# interface2.net
KiCad netlist of a schematic drawn in Altium Designer
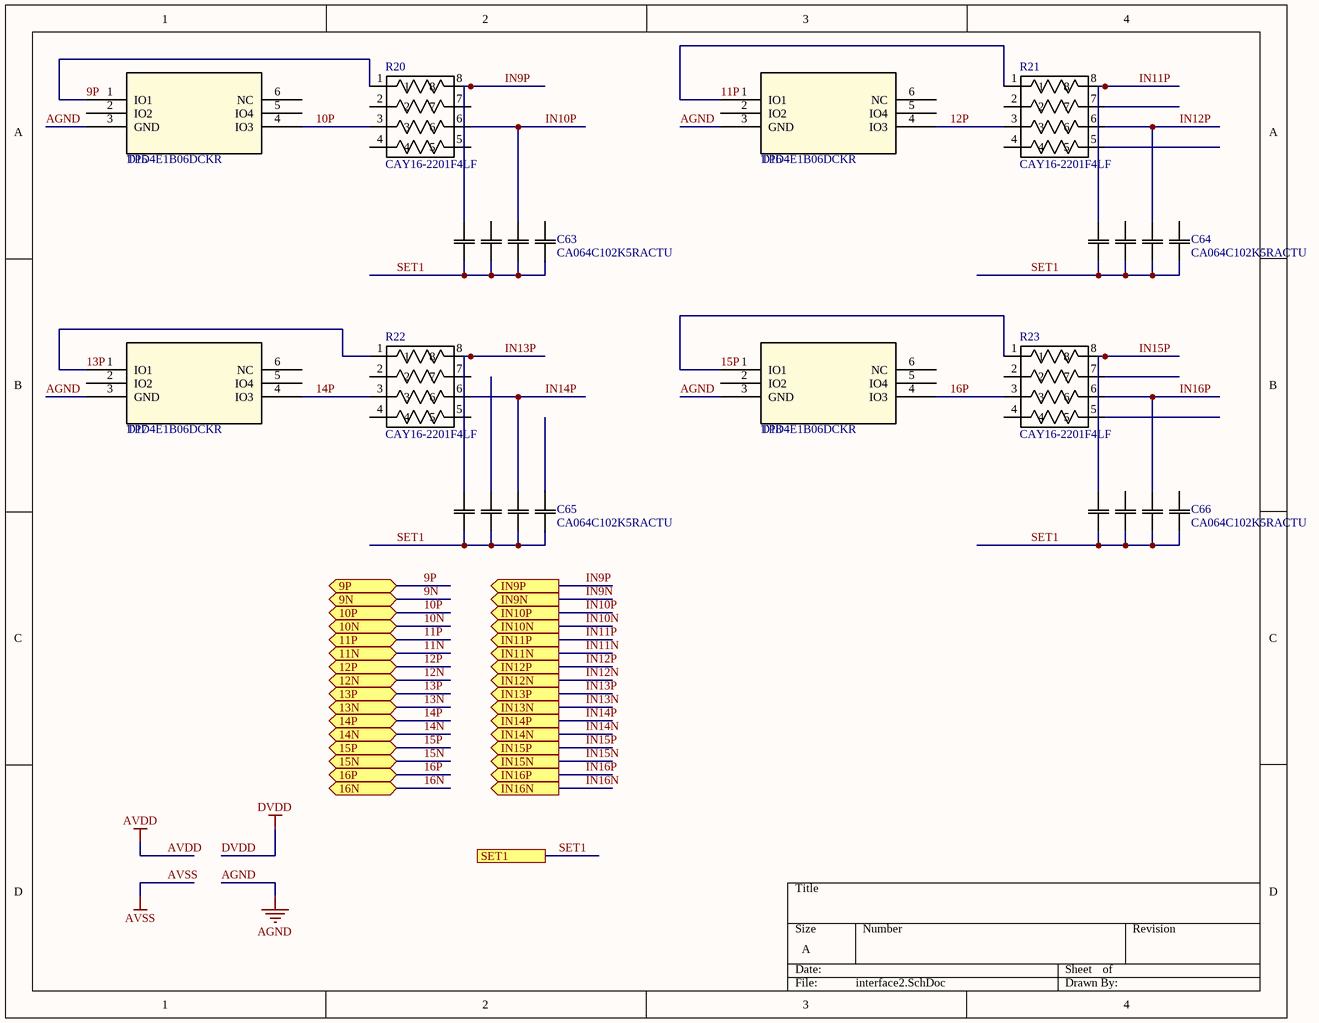
[diagram p0: interface2.SchDoc]

(export (version "E")
  (design (tool "Eeschema 10.0.6"))
  (components
    (comp (ref "C63")
      (value "CA064C102K5RACTU")
      (footprint "CA064")
      (description "CAP ARRAY 1000PF 50V X7R 0612")
      (fields (field (name "TOLERANCE") "10%"))
      (libsource (lib "EE_smallOB_BW_v1.0") (part "CA064C102K5RACTU"))
    )
    (comp (ref "C64")
      (value "CA064C102K5RACTU")
      (footprint "CA064")
      (description "CAP ARRAY 1000PF 50V X7R 0612")
      (fields (field (name "TOLERANCE") "10%"))
      (libsource (lib "EE_smallOB_BW_v1.0") (part "CA064C102K5RACTU"))
    )
    (comp (ref "C65")
      (value "CA064C102K5RACTU")
      (footprint "CA064")
      (description "CAP ARRAY 1000PF 50V X7R 0612")
      (fields (field (name "TOLERANCE") "10%"))
      (libsource (lib "EE_smallOB_BW_v1.0") (part "CA064C102K5RACTU"))
    )
    (comp (ref "C66")
      (value "CA064C102K5RACTU")
      (footprint "CA064")
      (description "CAP ARRAY 1000PF 50V X7R 0612")
      (fields (field (name "TOLERANCE") "10%"))
      (libsource (lib "EE_smallOB_BW_v1.0") (part "CA064C102K5RACTU"))
    )
    (comp (ref "D15")
      (value "TPD4E1B06DCKR")
      (footprint "DCK6")
      (description "TVS DIODE 5.5VWM 14.5VC SC70-6")
      (libsource (lib "EE_smallOB_BW_v1.0") (part "TPD4E1B06DCKR"))
    )
    (comp (ref "D16")
      (value "TPD4E1B06DCKR")
      (footprint "DCK6")
      (description "TVS DIODE 5.5VWM 14.5VC SC70-6")
      (libsource (lib "EE_smallOB_BW_v1.0") (part "TPD4E1B06DCKR"))
    )
    (comp (ref "D17")
      (value "TPD4E1B06DCKR")
      (footprint "DCK6")
      (description "TVS DIODE 5.5VWM 14.5VC SC70-6")
      (libsource (lib "EE_smallOB_BW_v1.0") (part "TPD4E1B06DCKR"))
    )
    (comp (ref "D18")
      (value "TPD4E1B06DCKR")
      (footprint "DCK6")
      (description "TVS DIODE 5.5VWM 14.5VC SC70-6")
      (libsource (lib "EE_smallOB_BW_v1.0") (part "TPD4E1B06DCKR"))
    )
    (comp (ref "R20")
      (value "CAY16-2201F4LF")
      (footprint "*RESCAXE80P320X160-8N")
      (description "BOURNS         CAY16-2201F4LF             RESISTOR, ARRAY-4, 2.2KOHM, 5%, SMD")
      (fields (field (name "TOLERANCE") "1%"))
      (libsource (lib "EE_smallOB_BW_v1.0") (part "CAY16-2201F4LF"))
    )
    (comp (ref "R21")
      (value "CAY16-2201F4LF")
      (footprint "*RESCAXE80P320X160-8N")
      (description "BOURNS         CAY16-2201F4LF             RESISTOR, ARRAY-4, 2.2KOHM, 5%, SMD")
      (fields (field (name "TOLERANCE") "1%"))
      (libsource (lib "EE_smallOB_BW_v1.0") (part "CAY16-2201F4LF"))
    )
    (comp (ref "R22")
      (value "CAY16-2201F4LF")
      (footprint "*RESCAXE80P320X160-8N")
      (description "BOURNS         CAY16-2201F4LF             RESISTOR, ARRAY-4, 2.2KOHM, 5%, SMD")
      (fields (field (name "TOLERANCE") "1%"))
      (libsource (lib "EE_smallOB_BW_v1.0") (part "CAY16-2201F4LF"))
    )
    (comp (ref "R23")
      (value "CAY16-2201F4LF")
      (footprint "*RESCAXE80P320X160-8N")
      (description "BOURNS         CAY16-2201F4LF             RESISTOR, ARRAY-4, 2.2KOHM, 5%, SMD")
      (fields (field (name "TOLERANCE") "1%"))
      (libsource (lib "EE_smallOB_BW_v1.0") (part "CAY16-2201F4LF"))
    )
  )
  (nets
    (net (code "2") (name "/9P") (class "Default")
      (node (ref "D15") (pin "1") (pinfunction "IO1_1") (pintype "passive"))
      (node (ref "R20") (pin "1") (pinfunction "1_1") (pintype "passive"))
    )
    (net (code "4") (name "/10P") (class "Default")
      (node (ref "D15") (pin "4") (pinfunction "IO3_4") (pintype "passive"))
      (node (ref "R20") (pin "3") (pinfunction "3_3") (pintype "passive"))
    )
    (net (code "6") (name "/11P") (class "Default")
      (node (ref "D16") (pin "1") (pinfunction "IO1_1") (pintype "passive"))
      (node (ref "R21") (pin "1") (pinfunction "1_1") (pintype "passive"))
    )
    (net (code "8") (name "/12P") (class "Default")
      (node (ref "D16") (pin "4") (pinfunction "IO3_4") (pintype "passive"))
      (node (ref "R21") (pin "3") (pinfunction "3_3") (pintype "passive"))
    )
    (net (code "10") (name "/13P") (class "Default")
      (node (ref "D17") (pin "1") (pinfunction "IO1_1") (pintype "passive"))
      (node (ref "R22") (pin "1") (pinfunction "1_1") (pintype "passive"))
    )
    (net (code "12") (name "/14P") (class "Default")
      (node (ref "D17") (pin "4") (pinfunction "IO3_4") (pintype "passive"))
      (node (ref "R22") (pin "3") (pinfunction "3_3") (pintype "passive"))
    )
    (net (code "14") (name "/15P") (class "Default")
      (node (ref "D18") (pin "1") (pinfunction "IO1_1") (pintype "passive"))
      (node (ref "R23") (pin "1") (pinfunction "1_1") (pintype "passive"))
    )
    (net (code "16") (name "/16P") (class "Default")
      (node (ref "D18") (pin "4") (pinfunction "IO3_4") (pintype "passive"))
      (node (ref "R23") (pin "3") (pinfunction "3_3") (pintype "passive"))
    )
    (net (code "18") (name "/IN9P") (class "Default")
      (node (ref "C63") (pin "8") (pinfunction "8_8") (pintype "passive"))
      (node (ref "R20") (pin "8") (pinfunction "8_8") (pintype "passive"))
    )
    (net (code "20") (name "/IN10P") (class "Default")
      (node (ref "C63") (pin "6") (pinfunction "6_6") (pintype "passive"))
      (node (ref "R20") (pin "6") (pinfunction "6_6") (pintype "passive"))
    )
    (net (code "22") (name "/IN11P") (class "Default")
      (node (ref "C64") (pin "8") (pinfunction "8_8") (pintype "passive"))
      (node (ref "R21") (pin "8") (pinfunction "8_8") (pintype "passive"))
    )
    (net (code "24") (name "/IN12P") (class "Default")
      (node (ref "C64") (pin "6") (pinfunction "6_6") (pintype "passive"))
      (node (ref "R21") (pin "6") (pinfunction "6_6") (pintype "passive"))
    )
    (net (code "26") (name "/IN13P") (class "Default")
      (node (ref "C65") (pin "8") (pinfunction "8_8") (pintype "passive"))
      (node (ref "R22") (pin "8") (pinfunction "8_8") (pintype "passive"))
    )
    (net (code "28") (name "/IN14P") (class "Default")
      (node (ref "C65") (pin "6") (pinfunction "6_6") (pintype "passive"))
      (node (ref "R22") (pin "6") (pinfunction "6_6") (pintype "passive"))
    )
    (net (code "30") (name "/IN15P") (class "Default")
      (node (ref "C66") (pin "8") (pinfunction "8_8") (pintype "passive"))
      (node (ref "R23") (pin "8") (pinfunction "8_8") (pintype "passive"))
    )
    (net (code "32") (name "/IN16P") (class "Default")
      (node (ref "C66") (pin "6") (pinfunction "6_6") (pintype "passive"))
      (node (ref "R23") (pin "6") (pinfunction "6_6") (pintype "passive"))
    )
    (net (code "33") (name "/SET1") (class "Default")
      (node (ref "C63") (pin "1") (pinfunction "1_1") (pintype "passive"))
      (node (ref "C63") (pin "2") (pinfunction "2_2") (pintype "passive"))
      (node (ref "C63") (pin "3") (pinfunction "3_3") (pintype "passive"))
      (node (ref "C63") (pin "4") (pinfunction "4_4") (pintype "passive"))
      (node (ref "C64") (pin "1") (pinfunction "1_1") (pintype "passive"))
      (node (ref "C64") (pin "2") (pinfunction "2_2") (pintype "passive"))
      (node (ref "C64") (pin "3") (pinfunction "3_3") (pintype "passive"))
      (node (ref "C64") (pin "4") (pinfunction "4_4") (pintype "passive"))
      (node (ref "C65") (pin "1") (pinfunction "1_1") (pintype "passive"))
      (node (ref "C65") (pin "2") (pinfunction "2_2") (pintype "passive"))
      (node (ref "C65") (pin "3") (pinfunction "3_3") (pintype "passive"))
      (node (ref "C65") (pin "4") (pinfunction "4_4") (pintype "passive"))
      (node (ref "C66") (pin "1") (pinfunction "1_1") (pintype "passive"))
      (node (ref "C66") (pin "2") (pinfunction "2_2") (pintype "passive"))
      (node (ref "C66") (pin "3") (pinfunction "3_3") (pintype "passive"))
      (node (ref "C66") (pin "4") (pinfunction "4_4") (pintype "passive"))
    )
    (net (code "34") (name "AGND") (class "Default")
      (node (ref "D15") (pin "3") (pinfunction "GND_3") (pintype "power_in"))
      (node (ref "D16") (pin "3") (pinfunction "GND_3") (pintype "power_in"))
      (node (ref "D17") (pin "3") (pinfunction "GND_3") (pintype "power_in"))
      (node (ref "D18") (pin "3") (pinfunction "GND_3") (pintype "power_in"))
    )
    (net (code "38") (name "unconnected-(C63-Pad5)") (class "Default")
      (node (ref "C63") (pin "5") (pinfunction "5_5") (pintype "passive"))
    )
    (net (code "39") (name "unconnected-(C63-Pad7)") (class "Default")
      (node (ref "C63") (pin "7") (pinfunction "7_7") (pintype "passive"))
    )
    (net (code "40") (name "unconnected-(C64-Pad5)") (class "Default")
      (node (ref "C64") (pin "5") (pinfunction "5_5") (pintype "passive"))
    )
    (net (code "41") (name "unconnected-(C64-Pad7)") (class "Default")
      (node (ref "C64") (pin "7") (pinfunction "7_7") (pintype "passive"))
    )
    (net (code "42") (name "unconnected-(C65-Pad5)") (class "Default")
      (node (ref "C65") (pin "5") (pinfunction "5_5") (pintype "passive"))
    )
    (net (code "43") (name "unconnected-(C65-Pad7)") (class "Default")
      (node (ref "C65") (pin "7") (pinfunction "7_7") (pintype "passive"))
    )
    (net (code "44") (name "unconnected-(C66-Pad5)") (class "Default")
      (node (ref "C66") (pin "5") (pinfunction "5_5") (pintype "passive"))
    )
    (net (code "45") (name "unconnected-(C66-Pad7)") (class "Default")
      (node (ref "C66") (pin "7") (pinfunction "7_7") (pintype "passive"))
    )
    (net (code "46") (name "unconnected-(D15-IO2-Pad2)") (class "Default")
      (node (ref "D15") (pin "2") (pinfunction "IO2_2") (pintype "passive"))
    )
    (net (code "47") (name "unconnected-(D15-IO4-Pad5)") (class "Default")
      (node (ref "D15") (pin "5") (pinfunction "IO4_5") (pintype "passive"))
    )
    (net (code "48") (name "unconnected-(D15-NC-Pad6)") (class "Default")
      (node (ref "D15") (pin "6") (pinfunction "NC_6") (pintype "passive"))
    )
    (net (code "49") (name "unconnected-(D16-IO2-Pad2)") (class "Default")
      (node (ref "D16") (pin "2") (pinfunction "IO2_2") (pintype "passive"))
    )
    (net (code "50") (name "unconnected-(D16-IO4-Pad5)") (class "Default")
      (node (ref "D16") (pin "5") (pinfunction "IO4_5") (pintype "passive"))
    )
    (net (code "51") (name "unconnected-(D16-NC-Pad6)") (class "Default")
      (node (ref "D16") (pin "6") (pinfunction "NC_6") (pintype "passive"))
    )
    (net (code "52") (name "unconnected-(D17-IO2-Pad2)") (class "Default")
      (node (ref "D17") (pin "2") (pinfunction "IO2_2") (pintype "passive"))
    )
    (net (code "53") (name "unconnected-(D17-IO4-Pad5)") (class "Default")
      (node (ref "D17") (pin "5") (pinfunction "IO4_5") (pintype "passive"))
    )
    (net (code "54") (name "unconnected-(D17-NC-Pad6)") (class "Default")
      (node (ref "D17") (pin "6") (pinfunction "NC_6") (pintype "passive"))
    )
    (net (code "55") (name "unconnected-(D18-IO2-Pad2)") (class "Default")
      (node (ref "D18") (pin "2") (pinfunction "IO2_2") (pintype "passive"))
    )
    (net (code "56") (name "unconnected-(D18-IO4-Pad5)") (class "Default")
      (node (ref "D18") (pin "5") (pinfunction "IO4_5") (pintype "passive"))
    )
    (net (code "57") (name "unconnected-(D18-NC-Pad6)") (class "Default")
      (node (ref "D18") (pin "6") (pinfunction "NC_6") (pintype "passive"))
    )
    (net (code "58") (name "unconnected-(R20-Pad2)") (class "Default")
      (node (ref "R20") (pin "2") (pinfunction "2_2") (pintype "passive"))
    )
    (net (code "59") (name "unconnected-(R20-Pad4)") (class "Default")
      (node (ref "R20") (pin "4") (pinfunction "4_4") (pintype "passive"))
    )
    (net (code "60") (name "unconnected-(R20-Pad5)") (class "Default")
      (node (ref "R20") (pin "5") (pinfunction "5_5") (pintype "passive"))
    )
    (net (code "61") (name "unconnected-(R20-Pad7)") (class "Default")
      (node (ref "R20") (pin "7") (pinfunction "7_7") (pintype "passive"))
    )
    (net (code "62") (name "unconnected-(R21-Pad2)") (class "Default")
      (node (ref "R21") (pin "2") (pinfunction "2_2") (pintype "passive"))
    )
    (net (code "63") (name "unconnected-(R21-Pad4)") (class "Default")
      (node (ref "R21") (pin "4") (pinfunction "4_4") (pintype "passive"))
    )
    (net (code "64") (name "unconnected-(R21-Pad5)") (class "Default")
      (node (ref "R21") (pin "5") (pinfunction "5_5") (pintype "passive"))
    )
    (net (code "65") (name "unconnected-(R21-Pad7)") (class "Default")
      (node (ref "R21") (pin "7") (pinfunction "7_7") (pintype "passive"))
    )
    (net (code "66") (name "unconnected-(R22-Pad2)") (class "Default")
      (node (ref "R22") (pin "2") (pinfunction "2_2") (pintype "passive"))
    )
    (net (code "67") (name "unconnected-(R22-Pad4)") (class "Default")
      (node (ref "R22") (pin "4") (pinfunction "4_4") (pintype "passive"))
    )
    (net (code "68") (name "unconnected-(R22-Pad5)") (class "Default")
      (node (ref "R22") (pin "5") (pinfunction "5_5") (pintype "passive"))
    )
    (net (code "69") (name "unconnected-(R22-Pad7)") (class "Default")
      (node (ref "R22") (pin "7") (pinfunction "7_7") (pintype "passive"))
    )
    (net (code "70") (name "unconnected-(R23-Pad2)") (class "Default")
      (node (ref "R23") (pin "2") (pinfunction "2_2") (pintype "passive"))
    )
    (net (code "71") (name "unconnected-(R23-Pad4)") (class "Default")
      (node (ref "R23") (pin "4") (pinfunction "4_4") (pintype "passive"))
    )
    (net (code "72") (name "unconnected-(R23-Pad5)") (class "Default")
      (node (ref "R23") (pin "5") (pinfunction "5_5") (pintype "passive"))
    )
    (net (code "73") (name "unconnected-(R23-Pad7)") (class "Default")
      (node (ref "R23") (pin "7") (pinfunction "7_7") (pintype "passive"))
    )
  )
)
